# 51shiyanban.net
KiCad netlist of a schematic drawn in Altium Designer
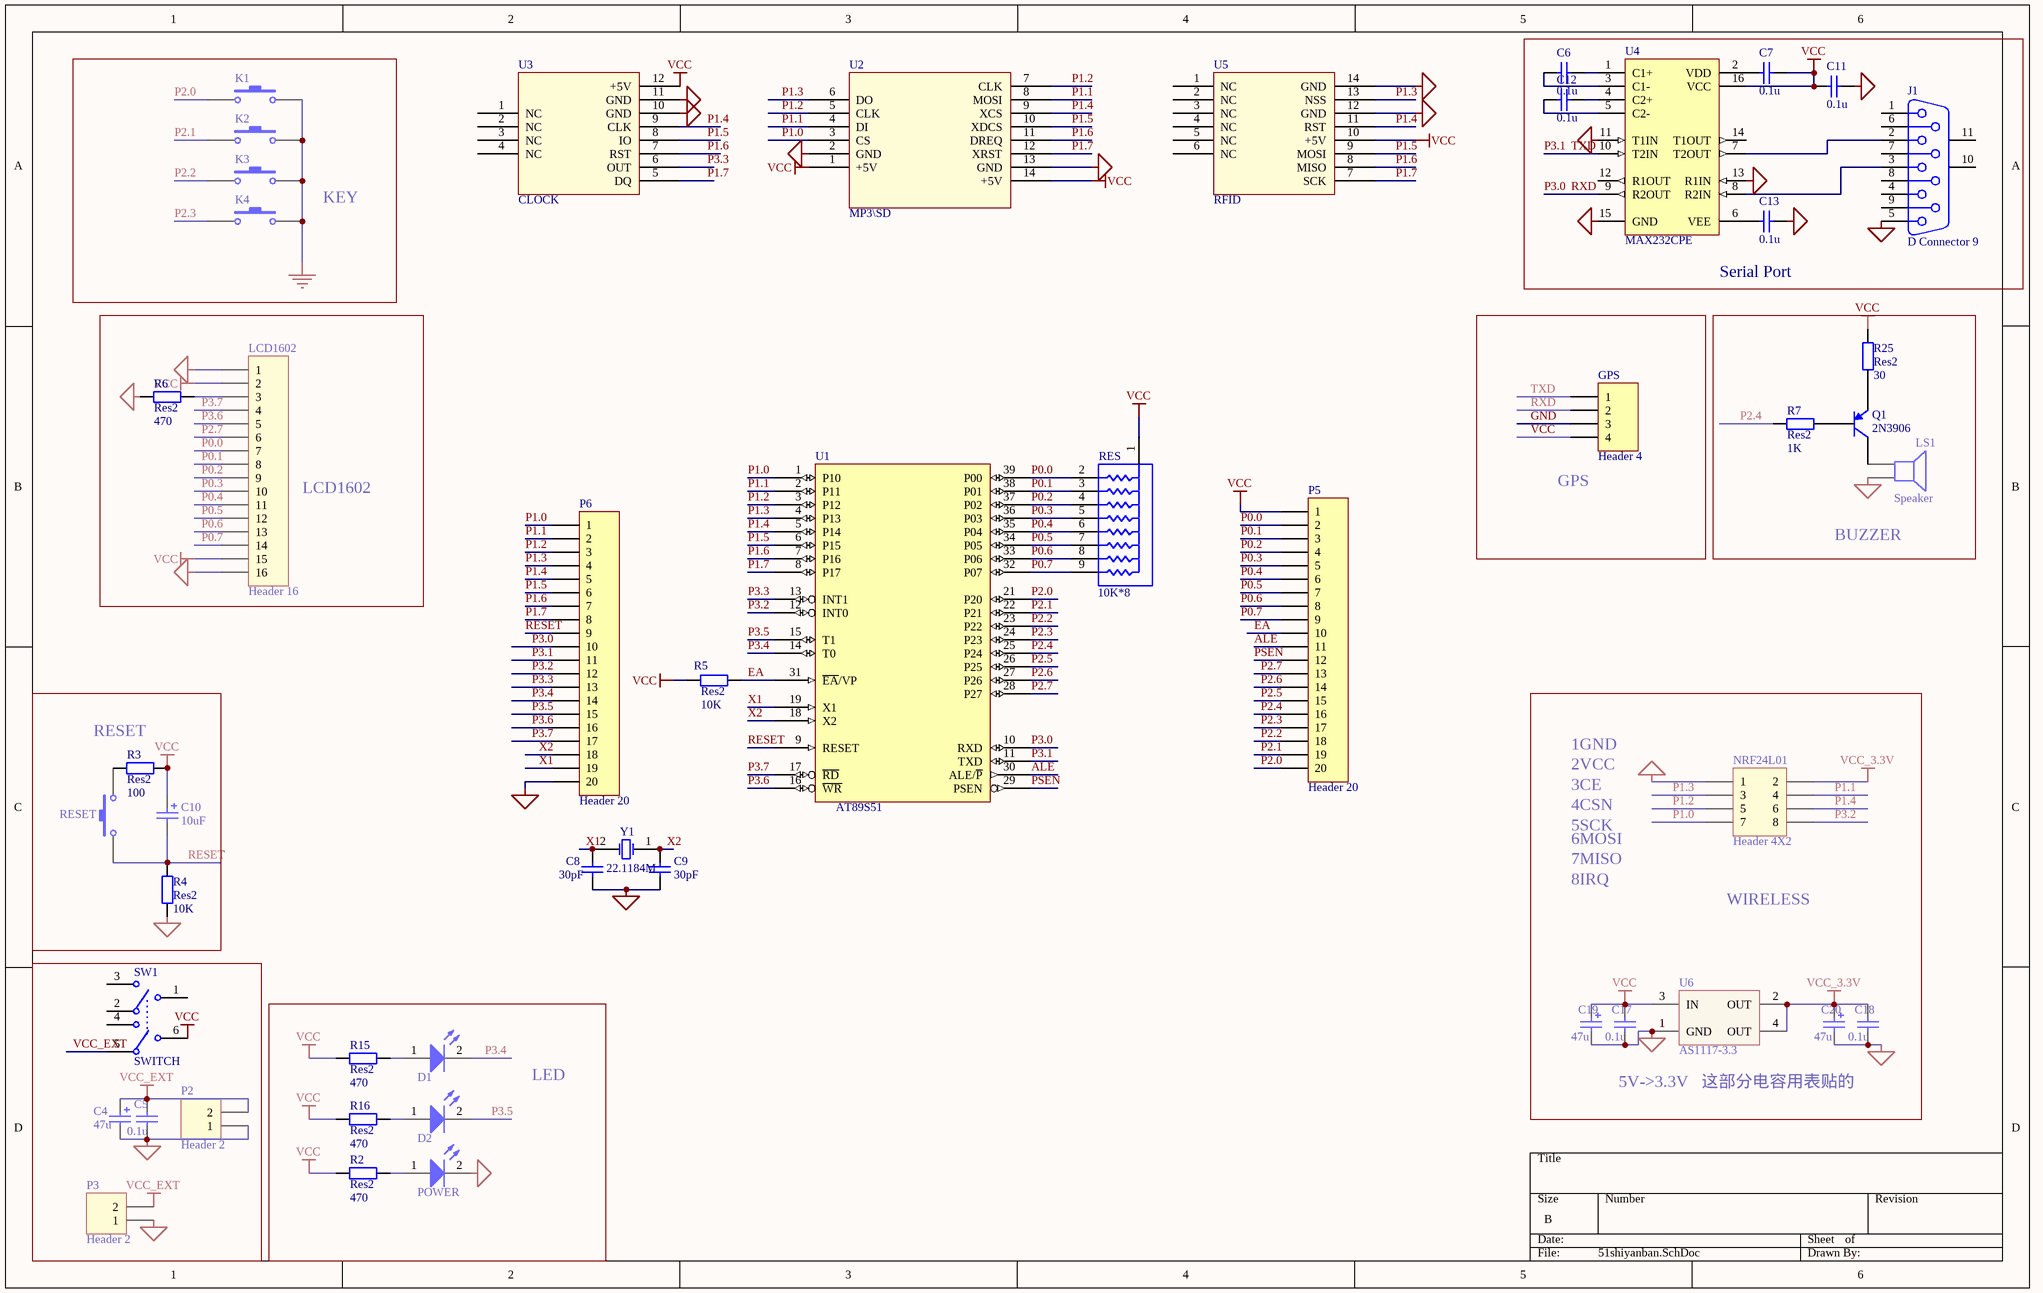
[diagram p0: 51shiyanban.SchDoc]

(export (version "E")
  (design (tool "Eeschema 10.0.6"))
  (components
    (comp (ref "C4")
      (value "47u")
      (footprint "CAP2_HT")
      (description "Polarized Capacitor (Radial)")
      (fields
        (field (name "MANUFACTURER") "Generic Components")
        (field (name "Comment") "Cap Pol1")
        (field (name "PUBLISHER") "Altium Hobart Technology Centre")
      )
      (libsource (lib "Miscellaneous Devices") (part "Cap Pol1"))
    )
    (comp (ref "C5")
      (value "0.1u")
      (footprint "CAP1_HT")
      (description "Capacitor")
      (fields
        (field (name "MANUFACTURER") "Generic Components")
        (field (name "PUBLISHER") "Altium Hobart Technology Centre")
      )
      (libsource (lib "Miscellaneous Devices") (part "Cap"))
    )
    (comp (ref "C6")
      (value "0.1u")
      (footprint "CAP1_HT")
      (description "Capacitor")
      (fields
        (field (name "MANUFACTURER") "Generic Components")
        (field (name "PUBLISHER") "Altium Hobart Technology Centre")
      )
      (libsource (lib "") (part "Cap_1"))
    )
    (comp (ref "C7")
      (value "0.1u")
      (footprint "CAP1_HT")
      (description "Capacitor")
      (fields
        (field (name "MANUFACTURER") "Generic Components")
        (field (name "PUBLISHER") "Altium Hobart Technology Centre")
      )
      (libsource (lib "") (part "Cap_1"))
    )
    (comp (ref "C8")
      (value "30pF")
      (footprint "CAP1_HT")
      (description "Capacitor")
      (fields
        (field (name "MANUFACTURER") "Generic Components")
        (field (name "Comment") "30P")
        (field (name "PUBLISHER") "Altium Hobart Technology Centre")
      )
      (libsource (lib "Miscellaneous Devices") (part "Cap"))
    )
    (comp (ref "C9")
      (value "30pF")
      (footprint "CAP1_HT")
      (description "Capacitor")
      (fields
        (field (name "MANUFACTURER") "Generic Components")
        (field (name "Comment") "30P")
        (field (name "PUBLISHER") "Altium Hobart Technology Centre")
      )
      (libsource (lib "Miscellaneous Devices") (part "Cap"))
    )
    (comp (ref "C10")
      (value "10uF")
      (footprint "CAP2_HT")
      (description "Polarized Capacitor (Radial)")
      (fields
        (field (name "MANUFACTURER") "Generic Components")
        (field (name "Comment") "Cap Pol1")
        (field (name "PUBLISHER") "Altium Hobart Technology Centre")
      )
      (libsource (lib "Miscellaneous Devices") (part "Cap Pol1"))
    )
    (comp (ref "C11")
      (value "0.1u")
      (footprint "CAP1_HT")
      (description "Capacitor")
      (fields
        (field (name "MANUFACTURER") "Generic Components")
        (field (name "PUBLISHER") "Altium Hobart Technology Centre")
      )
      (libsource (lib "") (part "Cap_1"))
    )
    (comp (ref "C12")
      (value "0.1u")
      (footprint "CAP1_HT")
      (description "Capacitor")
      (fields
        (field (name "MANUFACTURER") "Generic Components")
        (field (name "PUBLISHER") "Altium Hobart Technology Centre")
      )
      (libsource (lib "") (part "Cap_1"))
    )
    (comp (ref "C13")
      (value "0.1u")
      (footprint "CAP1_HT")
      (description "Capacitor")
      (fields
        (field (name "MANUFACTURER") "Generic Components")
        (field (name "PUBLISHER") "Altium Hobart Technology Centre")
      )
      (libsource (lib "") (part "Cap_1"))
    )
    (comp (ref "C17")
      (value "0.1u")
      (footprint "C0805")
      (description "Capacitor")
      (fields
        (field (name "MANUFACTURER") "Generic Components")
        (field (name "PUBLISHER") "Altium Hobart Technology Centre")
      )
      (libsource (lib "Miscellaneous Devices") (part "Cap"))
    )
    (comp (ref "C18")
      (value "0.1u")
      (footprint "C0805")
      (description "Capacitor")
      (fields
        (field (name "MANUFACTURER") "Generic Components")
        (field (name "PUBLISHER") "Altium Hobart Technology Centre")
      )
      (libsource (lib "Miscellaneous Devices") (part "Cap"))
    )
    (comp (ref "C19")
      (value "47u")
      (footprint "CAP_CA_D")
      (description "Polarized Capacitor (Radial)")
      (fields
        (field (name "MANUFACTURER") "Generic Components")
        (field (name "PUBLISHER") "Altium Hobart Technology Centre")
      )
      (libsource (lib "Miscellaneous Devices") (part "Cap Pol1"))
    )
    (comp (ref "C20")
      (value "47u")
      (footprint "CAP_CA_D")
      (description "Polarized Capacitor (Radial)")
      (fields
        (field (name "MANUFACTURER") "Generic Components")
        (field (name "PUBLISHER") "Altium Hobart Technology Centre")
      )
      (libsource (lib "Miscellaneous Devices") (part "Cap Pol1"))
    )
    (comp (ref "D1")
      (value "LED0")
      (footprint "LED1_HT")
      (description "Typical INFRARED GaAs LED")
      (fields
        (field (name "MANUFACTURER") "Generic Components")
        (field (name "PUBLISHER") "Altium Hobart Technology Centre")
      )
      (libsource (lib "Miscellaneous Devices") (part "LED0"))
    )
    (comp (ref "D2")
      (value "LED0")
      (footprint "LED1_HT")
      (description "Typical INFRARED GaAs LED")
      (fields
        (field (name "MANUFACTURER") "Generic Components")
        (field (name "PUBLISHER") "Altium Hobart Technology Centre")
      )
      (libsource (lib "Miscellaneous Devices") (part "LED0"))
    )
    (comp (ref "GPS")
      (value "Header 4")
      (footprint "HDR1X4")
      (description "Header, 4-Pin")
      (fields (field (name "PUBLISHER") "Altium Limited"))
      (libsource (lib "Miscellaneous Connectors") (part "Header 4"))
    )
    (comp (ref "J1")
      (value "D Connector 9")
      (footprint "DSUB1.385-2H9")
      (description "Receptacle Assembly, 9 Position, Right Angle")
      (fields (field (name "PUBLISHER") "Altium Limited"))
      (libsource (lib "Miscellaneous Connectors") (part "D Connector 9"))
    )
    (comp (ref "K1")
      (value "~")
      (footprint "KEY1_HT")
      (description "Switch")
      (fields (field (name "MANUFACTURER") "Generic Components"))
      (libsource (lib "Miscellaneous Devices") (part "SW-PB"))
    )
    (comp (ref "K2")
      (value "~")
      (footprint "KEY1_HT")
      (description "Switch")
      (fields (field (name "MANUFACTURER") "Generic Components"))
      (libsource (lib "Miscellaneous Devices") (part "SW-PB"))
    )
    (comp (ref "K3")
      (value "~")
      (footprint "KEY1_HT")
      (description "Switch")
      (fields (field (name "MANUFACTURER") "Generic Components"))
      (libsource (lib "Miscellaneous Devices") (part "SW-PB"))
    )
    (comp (ref "K4")
      (value "~")
      (footprint "KEY1_HT")
      (description "Switch")
      (fields (field (name "MANUFACTURER") "Generic Components"))
      (libsource (lib "Miscellaneous Devices") (part "SW-PB"))
    )
    (comp (ref "LCD1602")
      (value "Header 16")
      (footprint "HDR1X16")
      (description "Header, 16-Pin")
      (fields (field (name "PUBLISHER") "Altium Limited"))
      (libsource (lib "Miscellaneous Connectors") (part "Header 16"))
    )
    (comp (ref "LS1")
      (value "Speaker")
      (footprint "BUZZER_HT")
      (description "Loudspeaker")
      (fields (field (name "MANUFACTURER") "Generic Components"))
      (libsource (lib "Miscellaneous Devices") (part "Speaker"))
    )
    (comp (ref "NRF24L01")
      (value "Header 4X2")
      (footprint "HDR2X4")
      (description "Header, 4-Pin, Dual row")
      (fields (field (name "PUBLISHER") "Altium Limited"))
      (libsource (lib "Miscellaneous Connectors") (part "Header 4X2"))
    )
    (comp (ref "P2")
      (value "Header 2")
      (footprint "DCJACK")
      (description "Header, 2-Pin")
      (fields (field (name "MANUFACTURER") "Generic Components"))
      (libsource (lib "Miscellaneous Connectors") (part "Header 2"))
    )
    (comp (ref "P3")
      (value "Header 2")
      (footprint "Power_small")
      (description "Header, 2-Pin")
      (fields (field (name "MANUFACTURER") "Generic Components"))
      (libsource (lib "Miscellaneous Connectors") (part "Header 2"))
    )
    (comp (ref "P5")
      (value "Header 20")
      (footprint "HDR1X20")
      (description "Header, 20-Pin")
      (fields (field (name "PUBLISHER") "Altium Limited"))
      (libsource (lib "Miscellaneous Connectors") (part "Header 20"))
    )
    (comp (ref "P6")
      (value "Header 20")
      (footprint "HDR1X20")
      (description "Header, 20-Pin")
      (fields (field (name "PUBLISHER") "Altium Limited"))
      (libsource (lib "Miscellaneous Connectors") (part "Header 20"))
    )
    (comp (ref "POWER")
      (value "LED0")
      (footprint "LED1_HT")
      (description "Typical INFRARED GaAs LED")
      (fields
        (field (name "MANUFACTURER") "Generic Components")
        (field (name "PUBLISHER") "Altium Hobart Technology Centre")
      )
      (libsource (lib "Miscellaneous Devices") (part "LED0"))
    )
    (comp (ref "Q1")
      (value "2N3906")
      (footprint "Transistor")
      (description "PNP General Purpose Amplifier")
      (fields (field (name "PUBLISHER") "Altium Limited"))
      (libsource (lib "Miscellaneous Devices") (part "2N3906"))
    )
    (comp (ref "R2")
      (value "Res2")
      (footprint "AXIAL-0.4")
      (description "Resistor")
      (fields (field (name "ALTIUM_VALUE") "470") (field (name "PUBLISHER") "Altium Limited"))
      (libsource (lib "") (part "Res2_3"))
    )
    (comp (ref "R3")
      (value "Res2")
      (footprint "AXIAL-0.4")
      (description "Resistor")
      (fields (field (name "ALTIUM_VALUE") "100") (field (name "PUBLISHER") "Altium Limited"))
      (libsource (lib "Miscellaneous Devices") (part "Res2"))
    )
    (comp (ref "R4")
      (value "Res2")
      (footprint "AXIAL-0.4")
      (description "Resistor")
      (fields (field (name "ALTIUM_VALUE") "10K") (field (name "PUBLISHER") "Altium Limited"))
      (libsource (lib "") (part "Res2_1"))
    )
    (comp (ref "R5")
      (value "Res2")
      (footprint "AXIAL-0.4")
      (description "Resistor")
      (fields (field (name "ALTIUM_VALUE") "10K") (field (name "PUBLISHER") "Altium Limited"))
      (libsource (lib "Miscellaneous Devices") (part "Res2"))
    )
    (comp (ref "R6")
      (value "Res2")
      (footprint "AXIAL-0.4")
      (description "Resistor")
      (fields (field (name "ALTIUM_VALUE") "470") (field (name "PUBLISHER") "Altium Limited"))
      (libsource (lib "Miscellaneous Devices") (part "Res2"))
    )
    (comp (ref "R7")
      (value "Res2")
      (footprint "AXIAL-0.4")
      (description "Resistor")
      (fields (field (name "ALTIUM_VALUE") "1K") (field (name "PUBLISHER") "Altium Limited"))
      (libsource (lib "Miscellaneous Devices") (part "Res2"))
    )
    (comp (ref "R15")
      (value "Res2")
      (footprint "AXIAL-0.4")
      (description "Resistor")
      (fields (field (name "ALTIUM_VALUE") "470") (field (name "PUBLISHER") "Altium Limited"))
      (libsource (lib "") (part "Res2_3"))
    )
    (comp (ref "R16")
      (value "Res2")
      (footprint "AXIAL-0.4")
      (description "Resistor")
      (fields (field (name "ALTIUM_VALUE") "470") (field (name "PUBLISHER") "Altium Limited"))
      (libsource (lib "") (part "Res2_3"))
    )
    (comp (ref "R25")
      (value "Res2")
      (footprint "AXIAL-0.4")
      (description "Resistor")
      (fields (field (name "ALTIUM_VALUE") "30") (field (name "PUBLISHER") "Altium Limited"))
      (libsource (lib "") (part "Res2_2"))
    )
    (comp (ref "RES") (value "10K*8") (footprint "RES3_HT") (libsource (lib "Schlib1") (part "RESPACK")))
    (comp (ref "RESET")
      (value "~")
      (footprint "KEY1_HT")
      (description "Switch")
      (fields (field (name "MANUFACTURER") "Generic Components"))
      (libsource (lib "Miscellaneous Devices") (part "SW-PB"))
    )
    (comp (ref "SW1") (value "SWITCH") (footprint "DPDT-6") (libsource (lib "WENSHI") (part "SW-DPDT")))
    (comp (ref "U1") (value "AT89S51") (footprint "KDIP40_HT") (libsource (lib "*") (part "8031")))
    (comp (ref "U2") (value "MP~{3}SD") (footprint "MP3SD") (libsource (lib "Schlib1") (part "MP3SD")))
    (comp (ref "U3") (value "CLOCK") (footprint "CLOCK") (libsource (lib "Schlib1") (part "CLOCK")))
    (comp (ref "U4")
      (value "MAX232CPE")
      (footprint "DIP-16")
      (description "+5V Powered RS-232 Driver/Receiver")
      (fields (field (name "PUBLISHER") "Altium Limited"))
      (libsource (lib "Maxim Communication Transceiver") (part "MAX232CPE"))
    )
    (comp (ref "U5") (value "RFID") (footprint "RFID") (libsource (lib "Schlib1") (part "RFID")))
    (comp (ref "U6")
      (value "AS1117-3.3")
      (footprint "SOT-223")
      (libsource (lib "WENSHI") (part "AS1117-3.3"))
    )
    (comp (ref "Y1")
      (value "22.1184M")
      (footprint "XTAL1_HT")
      (description "Crystal Oscillator")
      (fields
        (field (name "MANUFACTURER") "Generic Components")
        (field (name "PUBLISHER") "Altium Hobart Technology Centre")
      )
      (libsource (lib "Miscellaneous Devices") (part "XTAL"))
    )
  )
  (nets
    (net (code "1") (name "/ALE") (class "Default")
      (node (ref "P5") (pin "11") (pinfunction "11_11") (pintype "passive"))
      (node (ref "U1") (pin "30") (pinfunction "ALE/~{P}_30") (pintype "output"))
    )
    (net (code "2") (name "/EA") (class "Default")
      (node (ref "P5") (pin "10") (pinfunction "10_10") (pintype "passive"))
      (node (ref "R5") (pin "1") (pinfunction "1_1") (pintype "passive"))
      (node (ref "U1") (pin "31") (pinfunction "~{EA}/VP_31") (pintype "input"))
    )
    (net (code "3") (name "/P0.0") (class "Default")
      (node (ref "LCD1602") (pin "7") (pinfunction "7_7") (pintype "passive"))
      (node (ref "P5") (pin "2") (pinfunction "2_2") (pintype "passive"))
      (node (ref "RES") (pin "2") (pinfunction "2_2") (pintype "passive"))
      (node (ref "U1") (pin "39") (pinfunction "P00_39") (pintype "bidirectional"))
    )
    (net (code "4") (name "/P0.1") (class "Default")
      (node (ref "LCD1602") (pin "8") (pinfunction "8_8") (pintype "passive"))
      (node (ref "P5") (pin "3") (pinfunction "3_3") (pintype "passive"))
      (node (ref "RES") (pin "3") (pinfunction "3_3") (pintype "passive"))
      (node (ref "U1") (pin "38") (pinfunction "P01_38") (pintype "bidirectional"))
    )
    (net (code "5") (name "/P0.2") (class "Default")
      (node (ref "LCD1602") (pin "9") (pinfunction "9_9") (pintype "passive"))
      (node (ref "P5") (pin "4") (pinfunction "4_4") (pintype "passive"))
      (node (ref "RES") (pin "4") (pinfunction "4_4") (pintype "passive"))
      (node (ref "U1") (pin "37") (pinfunction "P02_37") (pintype "bidirectional"))
    )
    (net (code "6") (name "/P0.3") (class "Default")
      (node (ref "LCD1602") (pin "10") (pinfunction "10_10") (pintype "passive"))
      (node (ref "P5") (pin "5") (pinfunction "5_5") (pintype "passive"))
      (node (ref "RES") (pin "5") (pinfunction "5_5") (pintype "passive"))
      (node (ref "U1") (pin "36") (pinfunction "P03_36") (pintype "bidirectional"))
    )
    (net (code "7") (name "/P0.4") (class "Default")
      (node (ref "LCD1602") (pin "11") (pinfunction "11_11") (pintype "passive"))
      (node (ref "P5") (pin "6") (pinfunction "6_6") (pintype "passive"))
      (node (ref "RES") (pin "6") (pinfunction "6_6") (pintype "passive"))
      (node (ref "U1") (pin "35") (pinfunction "P04_35") (pintype "bidirectional"))
    )
    (net (code "8") (name "/P0.5") (class "Default")
      (node (ref "LCD1602") (pin "12") (pinfunction "12_12") (pintype "passive"))
      (node (ref "P5") (pin "7") (pinfunction "7_7") (pintype "passive"))
      (node (ref "RES") (pin "7") (pinfunction "7_7") (pintype "passive"))
      (node (ref "U1") (pin "34") (pinfunction "P05_34") (pintype "bidirectional"))
    )
    (net (code "9") (name "/P0.6") (class "Default")
      (node (ref "LCD1602") (pin "13") (pinfunction "13_13") (pintype "passive"))
      (node (ref "P5") (pin "8") (pinfunction "8_8") (pintype "passive"))
      (node (ref "RES") (pin "8") (pinfunction "8_8") (pintype "passive"))
      (node (ref "U1") (pin "33") (pinfunction "P06_33") (pintype "bidirectional"))
    )
    (net (code "10") (name "/P0.7") (class "Default")
      (node (ref "LCD1602") (pin "14") (pinfunction "14_14") (pintype "passive"))
      (node (ref "P5") (pin "9") (pinfunction "9_9") (pintype "passive"))
      (node (ref "RES") (pin "9") (pinfunction "9_9") (pintype "passive"))
      (node (ref "U1") (pin "32") (pinfunction "P07_32") (pintype "bidirectional"))
    )
    (net (code "11") (name "/P1.0") (class "Default")
      (node (ref "NRF24L01") (pin "7") (pinfunction "7_7") (pintype "passive"))
      (node (ref "P6") (pin "1") (pinfunction "1_1") (pintype "passive"))
      (node (ref "U1") (pin "1") (pinfunction "P10_1") (pintype "bidirectional"))
      (node (ref "U2") (pin "3") (pinfunction "CS_3") (pintype "passive"))
    )
    (net (code "12") (name "/P1.1") (class "Default")
      (node (ref "NRF24L01") (pin "4") (pinfunction "4_4") (pintype "passive"))
      (node (ref "P6") (pin "2") (pinfunction "2_2") (pintype "passive"))
      (node (ref "U1") (pin "2") (pinfunction "P11_2") (pintype "bidirectional"))
      (node (ref "U2") (pin "4") (pinfunction "DI_4") (pintype "passive"))
      (node (ref "U2") (pin "8") (pinfunction "MOSI_8") (pintype "passive"))
    )
    (net (code "13") (name "/P1.2") (class "Default")
      (node (ref "NRF24L01") (pin "5") (pinfunction "5_5") (pintype "passive"))
      (node (ref "P6") (pin "3") (pinfunction "3_3") (pintype "passive"))
      (node (ref "U1") (pin "3") (pinfunction "P12_3") (pintype "bidirectional"))
      (node (ref "U2") (pin "5") (pinfunction "CLK_5") (pintype "passive"))
      (node (ref "U2") (pin "7") (pinfunction "CLK_7") (pintype "passive"))
    )
    (net (code "14") (name "/P1.3") (class "Default")
      (node (ref "NRF24L01") (pin "3") (pinfunction "3_3") (pintype "passive"))
      (node (ref "P6") (pin "4") (pinfunction "4_4") (pintype "passive"))
      (node (ref "U1") (pin "4") (pinfunction "P13_4") (pintype "bidirectional"))
      (node (ref "U2") (pin "6") (pinfunction "DO_6") (pintype "passive"))
      (node (ref "U5") (pin "13") (pinfunction "NSS_13") (pintype "passive"))
    )
    (net (code "15") (name "/P1.4") (class "Default")
      (node (ref "NRF24L01") (pin "6") (pinfunction "6_6") (pintype "passive"))
      (node (ref "P6") (pin "5") (pinfunction "5_5") (pintype "passive"))
      (node (ref "U1") (pin "5") (pinfunction "P14_5") (pintype "bidirectional"))
      (node (ref "U2") (pin "9") (pinfunction "XCS_9") (pintype "passive"))
      (node (ref "U3") (pin "9") (pinfunction "CLK_9") (pintype "passive"))
      (node (ref "U5") (pin "11") (pinfunction "RST_11") (pintype "passive"))
    )
    (net (code "16") (name "/P1.5") (class "Default")
      (node (ref "P6") (pin "6") (pinfunction "6_6") (pintype "passive"))
      (node (ref "U1") (pin "6") (pinfunction "P15_6") (pintype "bidirectional"))
      (node (ref "U2") (pin "10") (pinfunction "XDCS_10") (pintype "passive"))
      (node (ref "U3") (pin "8") (pinfunction "IO_8") (pintype "passive"))
      (node (ref "U5") (pin "9") (pinfunction "MOSI_9") (pintype "passive"))
    )
    (net (code "17") (name "/P1.6") (class "Default")
      (node (ref "P6") (pin "7") (pinfunction "7_7") (pintype "passive"))
      (node (ref "U1") (pin "7") (pinfunction "P16_7") (pintype "bidirectional"))
      (node (ref "U2") (pin "11") (pinfunction "DREQ_11") (pintype "passive"))
      (node (ref "U3") (pin "7") (pinfunction "RST_7") (pintype "passive"))
      (node (ref "U5") (pin "8") (pinfunction "MISO_8") (pintype "passive"))
    )
    (net (code "18") (name "/P1.7") (class "Default")
      (node (ref "P6") (pin "8") (pinfunction "8_8") (pintype "passive"))
      (node (ref "U1") (pin "8") (pinfunction "P17_8") (pintype "bidirectional"))
      (node (ref "U2") (pin "12") (pinfunction "XRST_12") (pintype "passive"))
      (node (ref "U3") (pin "5") (pinfunction "DQ_5") (pintype "passive"))
      (node (ref "U5") (pin "7") (pinfunction "SCK_7") (pintype "passive"))
    )
    (net (code "19") (name "/P2.0") (class "Default")
      (node (ref "K1") (pin "1") (pinfunction "1_1") (pintype "passive"))
      (node (ref "P5") (pin "20") (pinfunction "20_20") (pintype "passive"))
      (node (ref "U1") (pin "21") (pinfunction "P20_21") (pintype "bidirectional"))
    )
    (net (code "20") (name "/P2.1") (class "Default")
      (node (ref "K2") (pin "1") (pinfunction "1_1") (pintype "passive"))
      (node (ref "P5") (pin "19") (pinfunction "19_19") (pintype "passive"))
      (node (ref "U1") (pin "22") (pinfunction "P21_22") (pintype "bidirectional"))
    )
    (net (code "21") (name "/P2.2") (class "Default")
      (node (ref "K3") (pin "1") (pinfunction "1_1") (pintype "passive"))
      (node (ref "P5") (pin "18") (pinfunction "18_18") (pintype "passive"))
      (node (ref "U1") (pin "23") (pinfunction "P22_23") (pintype "bidirectional"))
    )
    (net (code "22") (name "/P2.3") (class "Default")
      (node (ref "K4") (pin "1") (pinfunction "1_1") (pintype "passive"))
      (node (ref "P5") (pin "17") (pinfunction "17_17") (pintype "passive"))
      (node (ref "U1") (pin "24") (pinfunction "P23_24") (pintype "bidirectional"))
    )
    (net (code "23") (name "/P2.4") (class "Default")
      (node (ref "P5") (pin "16") (pinfunction "16_16") (pintype "passive"))
      (node (ref "R7") (pin "2") (pinfunction "2_2") (pintype "passive"))
      (node (ref "U1") (pin "25") (pinfunction "P24_25") (pintype "bidirectional"))
    )
    (net (code "24") (name "/P2.5") (class "Default")
      (node (ref "P5") (pin "15") (pinfunction "15_15") (pintype "passive"))
      (node (ref "U1") (pin "26") (pinfunction "P25_26") (pintype "bidirectional"))
    )
    (net (code "25") (name "/P2.6") (class "Default")
      (node (ref "P5") (pin "14") (pinfunction "14_14") (pintype "passive"))
      (node (ref "U1") (pin "27") (pinfunction "P26_27") (pintype "bidirectional"))
    )
    (net (code "26") (name "/P2.7") (class "Default")
      (node (ref "LCD1602") (pin "6") (pinfunction "6_6") (pintype "passive"))
      (node (ref "P5") (pin "13") (pinfunction "13_13") (pintype "passive"))
      (node (ref "U1") (pin "28") (pinfunction "P27_28") (pintype "bidirectional"))
    )
    (net (code "27") (name "/P3.0") (class "Default")
      (node (ref "GPS") (pin "2") (pinfunction "2_2") (pintype "passive"))
      (node (ref "P6") (pin "10") (pinfunction "10_10") (pintype "passive"))
      (node (ref "U1") (pin "10") (pinfunction "RXD_10") (pintype "bidirectional"))
      (node (ref "U4") (pin "9") (pinfunction "R2OUT_9") (pintype "output"))
    )
    (net (code "28") (name "/P3.1") (class "Default")
      (node (ref "GPS") (pin "1") (pinfunction "1_1") (pintype "passive"))
      (node (ref "P6") (pin "11") (pinfunction "11_11") (pintype "passive"))
      (node (ref "U1") (pin "11") (pinfunction "TXD_11") (pintype "bidirectional"))
      (node (ref "U4") (pin "10") (pinfunction "T2IN_10") (pintype "input"))
    )
    (net (code "29") (name "/P3.2") (class "Default")
      (node (ref "NRF24L01") (pin "8") (pinfunction "8_8") (pintype "passive"))
      (node (ref "P6") (pin "12") (pinfunction "12_12") (pintype "passive"))
      (node (ref "U1") (pin "12") (pinfunction "INT0_12") (pintype "bidirectional"))
    )
    (net (code "30") (name "/P3.3") (class "Default")
      (node (ref "P6") (pin "13") (pinfunction "13_13") (pintype "passive"))
      (node (ref "U1") (pin "13") (pinfunction "INT1_13") (pintype "bidirectional"))
      (node (ref "U3") (pin "6") (pinfunction "OUT_6") (pintype "passive"))
    )
    (net (code "31") (name "/P3.4") (class "Default")
      (node (ref "D1") (pin "2") (pinfunction "K_2") (pintype "passive"))
      (node (ref "P6") (pin "14") (pinfunction "14_14") (pintype "passive"))
      (node (ref "U1") (pin "14") (pinfunction "T0_14") (pintype "bidirectional"))
    )
    (net (code "32") (name "/P3.5") (class "Default")
      (node (ref "D2") (pin "2") (pinfunction "K_2") (pintype "passive"))
      (node (ref "P6") (pin "15") (pinfunction "15_15") (pintype "passive"))
      (node (ref "U1") (pin "15") (pinfunction "T1_15") (pintype "bidirectional"))
    )
    (net (code "33") (name "/P3.6") (class "Default")
      (node (ref "LCD1602") (pin "5") (pinfunction "5_5") (pintype "passive"))
      (node (ref "P6") (pin "16") (pinfunction "16_16") (pintype "passive"))
      (node (ref "U1") (pin "16") (pinfunction "~{WR}_16") (pintype "bidirectional"))
    )
    (net (code "34") (name "/P3.7") (class "Default")
      (node (ref "LCD1602") (pin "4") (pinfunction "4_4") (pintype "passive"))
      (node (ref "P6") (pin "17") (pinfunction "17_17") (pintype "passive"))
      (node (ref "U1") (pin "17") (pinfunction "~{RD}_17") (pintype "bidirectional"))
    )
    (net (code "35") (name "/PSEN") (class "Default")
      (node (ref "P5") (pin "12") (pinfunction "12_12") (pintype "passive"))
      (node (ref "U1") (pin "29") (pinfunction "PSEN_29") (pintype "output"))
    )
    (net (code "36") (name "/RESET") (class "Default")
      (node (ref "C10") (pin "2") (pinfunction "2_2") (pintype "passive"))
      (node (ref "P6") (pin "9") (pinfunction "9_9") (pintype "passive"))
      (node (ref "R4") (pin "2") (pinfunction "2_2") (pintype "passive"))
      (node (ref "RESET") (pin "1") (pinfunction "1_1") (pintype "passive"))
      (node (ref "U1") (pin "9") (pinfunction "RESET_9") (pintype "input"))
    )
    (net (code "37") (name "/X1") (class "Default")
      (node (ref "C8") (pin "1") (pinfunction "1_1") (pintype "passive"))
      (node (ref "P6") (pin "19") (pinfunction "19_19") (pintype "passive"))
      (node (ref "U1") (pin "19") (pinfunction "X1_19") (pintype "input"))
      (node (ref "Y1") (pin "2") (pinfunction "OSC2_2") (pintype "passive"))
    )
    (net (code "38") (name "/X2") (class "Default")
      (node (ref "C9") (pin "1") (pinfunction "1_1") (pintype "passive"))
      (node (ref "P6") (pin "18") (pinfunction "18_18") (pintype "passive"))
      (node (ref "U1") (pin "18") (pinfunction "X2_18") (pintype "input"))
      (node (ref "Y1") (pin "1") (pinfunction "OSC1_1") (pintype "passive"))
    )
    (net (code "39") (name "GND") (class "Default")
      (node (ref "C11") (pin "2") (pinfunction "2_2") (pintype "passive"))
      (node (ref "C13") (pin "2") (pinfunction "2_2") (pintype "passive"))
      (node (ref "C17") (pin "2") (pinfunction "2_2") (pintype "passive"))
      (node (ref "C18") (pin "2") (pinfunction "2_2") (pintype "passive"))
      (node (ref "C19") (pin "2") (pinfunction "2_2") (pintype "passive"))
      (node (ref "C20") (pin "2") (pinfunction "2_2") (pintype "passive"))
      (node (ref "C4") (pin "2") (pinfunction "2_2") (pintype "passive"))
      (node (ref "C5") (pin "2") (pinfunction "2_2") (pintype "passive"))
      (node (ref "C8") (pin "2") (pinfunction "2_2") (pintype "passive"))
      (node (ref "C9") (pin "2") (pinfunction "2_2") (pintype "passive"))
      (node (ref "GPS") (pin "3") (pinfunction "3_3") (pintype "passive"))
      (node (ref "J1") (pin "5") (pinfunction "5_5") (pintype "passive"))
      (node (ref "K1") (pin "2") (pinfunction "2_2") (pintype "passive"))
      (node (ref "K2") (pin "2") (pinfunction "2_2") (pintype "passive"))
      (node (ref "K3") (pin "2") (pinfunction "2_2") (pintype "passive"))
      (node (ref "K4") (pin "2") (pinfunction "2_2") (pintype "passive"))
      (node (ref "LCD1602") (pin "1") (pinfunction "1_1") (pintype "passive"))
      (node (ref "LCD1602") (pin "16") (pinfunction "16_16") (pintype "passive"))
      (node (ref "LS1") (pin "2") (pinfunction "2_2") (pintype "passive"))
      (node (ref "NRF24L01") (pin "1") (pinfunction "1_1") (pintype "passive"))
      (node (ref "P2") (pin "1") (pinfunction "1_1") (pintype "passive"))
      (node (ref "P3") (pin "1") (pinfunction "1_1") (pintype "passive"))
      (node (ref "P6") (pin "20") (pinfunction "20_20") (pintype "passive"))
      (node (ref "POWER") (pin "2") (pinfunction "K_2") (pintype "passive"))
      (node (ref "R4") (pin "1") (pinfunction "1_1") (pintype "passive"))
      (node (ref "R6") (pin "2") (pinfunction "2_2") (pintype "passive"))
      (node (ref "U1") (pin "20") (pinfunction "GND_20") (pintype "power_in"))
      (node (ref "U2") (pin "13") (pinfunction "GND_13") (pintype "passive"))
      (node (ref "U2") (pin "2") (pinfunction "GND_2") (pintype "passive"))
      (node (ref "U3") (pin "10") (pinfunction "GND_10") (pintype "passive"))
      (node (ref "U3") (pin "11") (pinfunction "GND_11") (pintype "passive"))
      (node (ref "U4") (pin "11") (pinfunction "T1IN_11") (pintype "input"))
      (node (ref "U4") (pin "13") (pinfunction "R1IN_13") (pintype "input"))
      (node (ref "U4") (pin "15") (pinfunction "GND_15") (pintype "power_in"))
      (node (ref "U5") (pin "12") (pinfunction "GND_12") (pintype "passive"))
      (node (ref "U5") (pin "14") (pinfunction "GND_14") (pintype "passive"))
      (node (ref "U6") (pin "1") (pinfunction "GND_1") (pintype "passive"))
    )
    (net (code "40") (name "Net-(D1-A)") (class "Default")
      (node (ref "D1") (pin "1") (pinfunction "A_1") (pintype "passive"))
      (node (ref "R15") (pin "2") (pinfunction "2_2") (pintype "passive"))
    )
    (net (code "41") (name "Net-(D2-A)") (class "Default")
      (node (ref "D2") (pin "1") (pinfunction "A_1") (pintype "passive"))
      (node (ref "R16") (pin "2") (pinfunction "2_2") (pintype "passive"))
    )
    (net (code "42") (name "Net-(LCD1602-Pad3)") (class "Default")
      (node (ref "LCD1602") (pin "3") (pinfunction "3_3") (pintype "passive"))
      (node (ref "R6") (pin "1") (pinfunction "1_1") (pintype "passive"))
    )
    (net (code "43") (name "Net-(POWER-A)") (class "Default")
      (node (ref "POWER") (pin "1") (pinfunction "A_1") (pintype "passive"))
      (node (ref "R2") (pin "2") (pinfunction "2_2") (pintype "passive"))
    )
    (net (code "44") (name "Net-(Q1-B)") (class "Default")
      (node (ref "Q1") (pin "2") (pinfunction "B_2") (pintype "passive"))
      (node (ref "R7") (pin "1") (pinfunction "1_1") (pintype "passive"))
    )
    (net (code "45") (name "Net-(Q1-C)") (class "Default")
      (node (ref "LS1") (pin "1") (pinfunction "1_1") (pintype "passive"))
      (node (ref "Q1") (pin "3") (pinfunction "C_3") (pintype "passive"))
    )
    (net (code "46") (name "Net-(Q1-E)") (class "Default")
      (node (ref "Q1") (pin "1") (pinfunction "E_1") (pintype "passive"))
      (node (ref "R25") (pin "2") (pinfunction "2_2") (pintype "passive"))
    )
    (net (code "47") (name "Net-(R3-Pad2)") (class "Default")
      (node (ref "R3") (pin "2") (pinfunction "2_2") (pintype "passive"))
      (node (ref "RESET") (pin "2") (pinfunction "2_2") (pintype "passive"))
    )
    (net (code "48") (name "Net-(U4-C1+)") (class "Default")
      (node (ref "C6") (pin "2") (pinfunction "2_2") (pintype "passive"))
      (node (ref "U4") (pin "1") (pinfunction "C1+_1") (pintype "passive"))
    )
    (net (code "49") (name "Net-(U4-C1-)") (class "Default")
      (node (ref "C6") (pin "1") (pinfunction "1_1") (pintype "passive"))
      (node (ref "U4") (pin "3") (pinfunction "C1-_3") (pintype "passive"))
    )
    (net (code "50") (name "Net-(U4-C2+)") (class "Default")
      (node (ref "C12") (pin "2") (pinfunction "2_2") (pintype "passive"))
      (node (ref "U4") (pin "4") (pinfunction "C2+_4") (pintype "passive"))
    )
    (net (code "51") (name "Net-(U4-C2-)") (class "Default")
      (node (ref "C12") (pin "1") (pinfunction "1_1") (pintype "passive"))
      (node (ref "U4") (pin "5") (pinfunction "C2-_5") (pintype "passive"))
    )
    (net (code "52") (name "Net-(U4-R2IN)") (class "Default")
      (node (ref "J1") (pin "3") (pinfunction "3_3") (pintype "passive"))
      (node (ref "U4") (pin "8") (pinfunction "R2IN_8") (pintype "input"))
    )
    (net (code "53") (name "Net-(U4-T2OUT)") (class "Default")
      (node (ref "J1") (pin "2") (pinfunction "2_2") (pintype "passive"))
      (node (ref "U4") (pin "7") (pinfunction "T2OUT_7") (pintype "output"))
    )
    (net (code "54") (name "Net-(U4-VDD)") (class "Default")
      (node (ref "C7") (pin "1") (pinfunction "1_1") (pintype "passive"))
      (node (ref "U4") (pin "2") (pinfunction "VDD_2") (pintype "power_in"))
    )
    (net (code "55") (name "Net-(U4-VEE)") (class "Default")
      (node (ref "C13") (pin "1") (pinfunction "1_1") (pintype "passive"))
      (node (ref "U4") (pin "6") (pinfunction "VEE_6") (pintype "power_in"))
    )
    (net (code "56") (name "VCC") (class "Default")
      (node (ref "C10") (pin "1") (pinfunction "1_1") (pintype "passive"))
      (node (ref "C11") (pin "1") (pinfunction "1_1") (pintype "passive"))
      (node (ref "C17") (pin "1") (pinfunction "1_1") (pintype "passive"))
      (node (ref "C19") (pin "1") (pinfunction "1_1") (pintype "passive"))
      (node (ref "C7") (pin "2") (pinfunction "2_2") (pintype "passive"))
      (node (ref "GPS") (pin "4") (pinfunction "4_4") (pintype "passive"))
      (node (ref "LCD1602") (pin "15") (pinfunction "15_15") (pintype "passive"))
      (node (ref "LCD1602") (pin "2") (pinfunction "2_2") (pintype "passive"))
      (node (ref "P5") (pin "1") (pinfunction "1_1") (pintype "passive"))
      (node (ref "R15") (pin "1") (pinfunction "1_1") (pintype "passive"))
      (node (ref "R16") (pin "1") (pinfunction "1_1") (pintype "passive"))
      (node (ref "R2") (pin "1") (pinfunction "1_1") (pintype "passive"))
      (node (ref "R25") (pin "1") (pinfunction "1_1") (pintype "passive"))
      (node (ref "R3") (pin "1") (pinfunction "1_1") (pintype "passive"))
      (node (ref "R5") (pin "2") (pinfunction "2_2") (pintype "passive"))
      (node (ref "RES") (pin "1") (pinfunction "1_1") (pintype "passive"))
      (node (ref "SW1") (pin "6") (pinfunction "6_6") (pintype "passive"))
      (node (ref "U1") (pin "40") (pinfunction "VCC_40") (pintype "power_in"))
      (node (ref "U2") (pin "1") (pinfunction "+5V_1") (pintype "passive"))
      (node (ref "U2") (pin "14") (pinfunction "+5V_14") (pintype "passive"))
      (node (ref "U3") (pin "12") (pinfunction "+5V_12") (pintype "passive"))
      (node (ref "U4") (pin "16") (pinfunction "VCC_16") (pintype "power_in"))
      (node (ref "U5") (pin "10") (pinfunction "+5V_10") (pintype "passive"))
      (node (ref "U6") (pin "3") (pinfunction "IN_3") (pintype "passive"))
    )
    (net (code "57") (name "VCC_3.3V") (class "Default")
      (node (ref "C18") (pin "1") (pinfunction "1_1") (pintype "passive"))
      (node (ref "C20") (pin "1") (pinfunction "1_1") (pintype "passive"))
      (node (ref "NRF24L01") (pin "2") (pinfunction "2_2") (pintype "passive"))
      (node (ref "U6") (pin "2") (pinfunction "OUT_2") (pintype "passive"))
      (node (ref "U6") (pin "4") (pinfunction "OUT_4") (pintype "passive"))
    )
    (net (code "58") (name "VCC_EXT") (class "Default")
      (node (ref "C4") (pin "1") (pinfunction "1_1") (pintype "passive"))
      (node (ref "C5") (pin "1") (pinfunction "1_1") (pintype "passive"))
      (node (ref "P2") (pin "2") (pinfunction "2_2") (pintype "passive"))
      (node (ref "P3") (pin "2") (pinfunction "2_2") (pintype "passive"))
      (node (ref "SW1") (pin "5") (pinfunction "5_5") (pintype "passive"))
    )
    (net (code "59") (name "unconnected-(J1-MH1-Pad10)") (class "Default")
      (node (ref "J1") (pin "10") (pinfunction "MH1_10") (pintype "passive"))
    )
    (net (code "60") (name "unconnected-(J1-MH2-Pad11)") (class "Default")
      (node (ref "J1") (pin "11") (pinfunction "MH2_11") (pintype "passive"))
    )
    (net (code "61") (name "unconnected-(J1-Pad1)") (class "Default")
      (node (ref "J1") (pin "1") (pinfunction "1_1") (pintype "passive"))
    )
    (net (code "62") (name "unconnected-(J1-Pad4)") (class "Default")
      (node (ref "J1") (pin "4") (pinfunction "4_4") (pintype "passive"))
    )
    (net (code "63") (name "unconnected-(J1-Pad6)") (class "Default")
      (node (ref "J1") (pin "6") (pinfunction "6_6") (pintype "passive"))
    )
    (net (code "64") (name "unconnected-(J1-Pad7)") (class "Default")
      (node (ref "J1") (pin "7") (pinfunction "7_7") (pintype "passive"))
    )
    (net (code "65") (name "unconnected-(J1-Pad8)") (class "Default")
      (node (ref "J1") (pin "8") (pinfunction "8_8") (pintype "passive"))
    )
    (net (code "66") (name "unconnected-(J1-Pad9)") (class "Default")
      (node (ref "J1") (pin "9") (pinfunction "9_9") (pintype "passive"))
    )
    (net (code "67") (name "unconnected-(SW1-Pad1)") (class "Default")
      (node (ref "SW1") (pin "1") (pinfunction "1_1") (pintype "passive"))
    )
    (net (code "68") (name "unconnected-(SW1-Pad2)") (class "Default")
      (node (ref "SW1") (pin "2") (pinfunction "2_2") (pintype "passive"))
    )
    (net (code "69") (name "unconnected-(SW1-Pad3)") (class "Default")
      (node (ref "SW1") (pin "3") (pinfunction "3_3") (pintype "passive"))
    )
    (net (code "70") (name "unconnected-(SW1-Pad4)") (class "Default")
      (node (ref "SW1") (pin "4") (pinfunction "4_4") (pintype "passive"))
    )
    (net (code "71") (name "unconnected-(U3-NC-Pad1)") (class "Default")
      (node (ref "U3") (pin "1") (pinfunction "NC_1") (pintype "passive"))
    )
    (net (code "72") (name "unconnected-(U3-NC-Pad2)") (class "Default")
      (node (ref "U3") (pin "2") (pinfunction "NC_2") (pintype "passive"))
    )
    (net (code "73") (name "unconnected-(U3-NC-Pad3)") (class "Default")
      (node (ref "U3") (pin "3") (pinfunction "NC_3") (pintype "passive"))
    )
    (net (code "74") (name "unconnected-(U3-NC-Pad4)") (class "Default")
      (node (ref "U3") (pin "4") (pinfunction "NC_4") (pintype "passive"))
    )
    (net (code "75") (name "unconnected-(U4-R1OUT-Pad12)") (class "Default")
      (node (ref "U4") (pin "12") (pinfunction "R1OUT_12") (pintype "output"))
    )
    (net (code "76") (name "unconnected-(U4-T1OUT-Pad14)") (class "Default")
      (node (ref "U4") (pin "14") (pinfunction "T1OUT_14") (pintype "output"))
    )
    (net (code "77") (name "unconnected-(U5-NC-Pad1)") (class "Default")
      (node (ref "U5") (pin "1") (pinfunction "NC_1") (pintype "passive"))
    )
    (net (code "78") (name "unconnected-(U5-NC-Pad2)") (class "Default")
      (node (ref "U5") (pin "2") (pinfunction "NC_2") (pintype "passive"))
    )
    (net (code "79") (name "unconnected-(U5-NC-Pad3)") (class "Default")
      (node (ref "U5") (pin "3") (pinfunction "NC_3") (pintype "passive"))
    )
    (net (code "80") (name "unconnected-(U5-NC-Pad4)") (class "Default")
      (node (ref "U5") (pin "4") (pinfunction "NC_4") (pintype "passive"))
    )
    (net (code "81") (name "unconnected-(U5-NC-Pad5)") (class "Default")
      (node (ref "U5") (pin "5") (pinfunction "NC_5") (pintype "passive"))
    )
    (net (code "82") (name "unconnected-(U5-NC-Pad6)") (class "Default")
      (node (ref "U5") (pin "6") (pinfunction "NC_6") (pintype "passive"))
    )
  )
)
